# touch_rev2.net
KiCad netlist of a schematic drawn in EAGLE
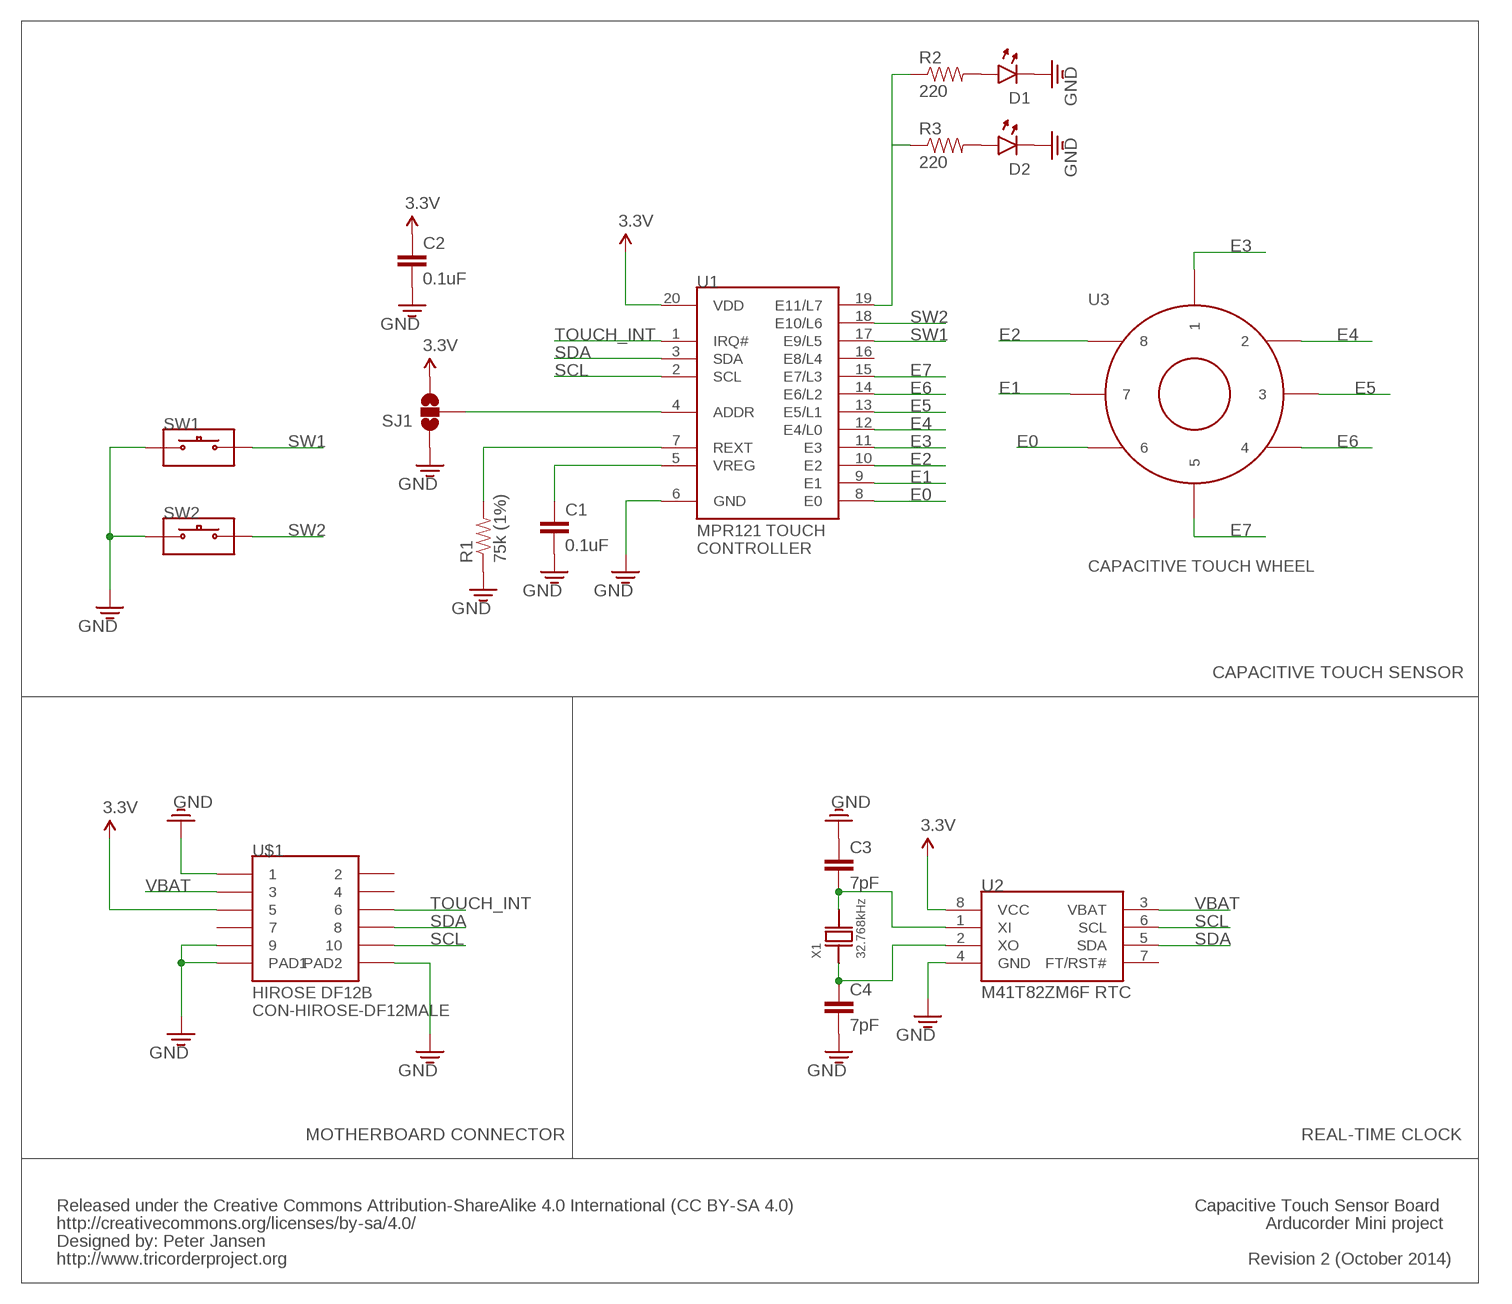
[diagram p0: schematic, sheet 1]

(export (version "E")
  (design (tool "Eeschema 10.0.6"))
  (components
    (comp (ref "C1")
      (value "0.1uF")
      (footprint "eagle-import:0603")
      (libsource (lib "eagle-import") (part "CAP0603"))
    )
    (comp (ref "C2")
      (value "0.1uF")
      (footprint "eagle-import:0603")
      (libsource (lib "eagle-import") (part "CAP0603"))
    )
    (comp (ref "C3")
      (value "7pF")
      (footprint "eagle-import:0603")
      (libsource (lib "eagle-import") (part "CAP0603"))
    )
    (comp (ref "C4")
      (value "7pF")
      (footprint "eagle-import:0603")
      (libsource (lib "eagle-import") (part "CAP0603"))
    )
    (comp (ref "D1")
      (value "0605-LED")
      (footprint "eagle-import:0603-LED")
      (libsource (lib "eagle-import") (part "0605-LED"))
    )
    (comp (ref "D2")
      (value "0605-LED")
      (footprint "eagle-import:0603-LED")
      (libsource (lib "eagle-import") (part "0605-LED"))
    )
    (comp (ref "R1")
      (value "75k (1%)")
      (footprint "eagle-import:0603")
      (libsource (lib "eagle-import") (part "RESISTOR0603"))
    )
    (comp (ref "R2")
      (value "220")
      (footprint "eagle-import:0603")
      (libsource (lib "eagle-import") (part "RESISTOR0603"))
    )
    (comp (ref "R3")
      (value "220")
      (footprint "eagle-import:0603")
      (libsource (lib "eagle-import") (part "RESISTOR0603"))
    )
    (comp (ref "SJ1")
      (value "SOLDERJUMPER_2WAYPASTE1&2")
      (footprint "eagle-import:SJ_3_PASTE1&2")
      (libsource (lib "eagle-import") (part "SOLDERJUMPER_2WAYPASTE1&2"))
    )
    (comp (ref "SW1")
      (value "SWITCH")
      (footprint "eagle-import:KMT071")
      (libsource (lib "eagle-import") (part "SWITCH"))
    )
    (comp (ref "SW2")
      (value "SWITCH")
      (footprint "eagle-import:KMT071")
      (libsource (lib "eagle-import") (part "SWITCH"))
    )
    (comp (ref "U$1")
      (value "CON-HIROSE-DF12MALE")
      (footprint "eagle-import:DF12B(3.0)-10DS-0.5V(86)")
      (libsource (lib "eagle-import") (part "CON-HIROSE-DF12MALE"))
    )
    (comp (ref "U1")
      (value "MPR121-TOUCH-CONTROLLER")
      (footprint "eagle-import:QFN-3X3-20")
      (libsource (lib "eagle-import") (part "MPR121-TOUCH-CONTROLLER"))
    )
    (comp (ref "U2")
      (value "M41T82ZM6F")
      (footprint "eagle-import:8-SOIC")
      (libsource (lib "eagle-import") (part "M41T82ZM6F"))
    )
    (comp (ref "U3")
      (value "CAPACITIVE-WHEEL-8")
      (footprint "eagle-import:CAPACITIVE-WHEEL-8")
      (libsource (lib "eagle-import") (part "CAPACITIVE-WHEEL-8"))
    )
    (comp (ref "X1")
      (value "32.768kHz")
      (footprint "eagle-import:CRYSTAL-9HT10")
      (libsource (lib "eagle-import") (part "CRYSTAL"))
    )
  )
  (nets
    (net (code "1") (name "/E0") (class "Default")
      (node (ref "U1") (pin "8") (pinfunction "E0_8") (pintype "bidirectional"))
      (node (ref "U3") (pin "6") (pinfunction "6_6") (pintype "bidirectional"))
    )
    (net (code "2") (name "/E1") (class "Default")
      (node (ref "U1") (pin "9") (pinfunction "E1_9") (pintype "bidirectional"))
      (node (ref "U3") (pin "7") (pinfunction "7_7") (pintype "bidirectional"))
    )
    (net (code "3") (name "/E2") (class "Default")
      (node (ref "U1") (pin "10") (pinfunction "E2_10") (pintype "bidirectional"))
      (node (ref "U3") (pin "8") (pinfunction "8_8") (pintype "bidirectional"))
    )
    (net (code "4") (name "/E3") (class "Default")
      (node (ref "U1") (pin "11") (pinfunction "E3_11") (pintype "bidirectional"))
      (node (ref "U3") (pin "1") (pinfunction "1_1") (pintype "bidirectional"))
    )
    (net (code "5") (name "/E4") (class "Default")
      (node (ref "U1") (pin "12") (pinfunction "E4/L0_12") (pintype "bidirectional"))
      (node (ref "U3") (pin "2") (pinfunction "2_2") (pintype "bidirectional"))
    )
    (net (code "6") (name "/E5") (class "Default")
      (node (ref "U1") (pin "13") (pinfunction "E5/L1_13") (pintype "bidirectional"))
      (node (ref "U3") (pin "3") (pinfunction "3_3") (pintype "bidirectional"))
    )
    (net (code "7") (name "/E6") (class "Default")
      (node (ref "U1") (pin "14") (pinfunction "E6/L2_14") (pintype "bidirectional"))
      (node (ref "U3") (pin "4") (pinfunction "4_4") (pintype "bidirectional"))
    )
    (net (code "8") (name "/E7") (class "Default")
      (node (ref "U1") (pin "15") (pinfunction "E7/L3_15") (pintype "bidirectional"))
      (node (ref "U3") (pin "5") (pinfunction "5_5") (pintype "bidirectional"))
    )
    (net (code "9") (name "/SCL") (class "Default")
      (node (ref "U$1") (pin "10") (pinfunction "10_10") (pintype "bidirectional"))
      (node (ref "U1") (pin "2") (pinfunction "SCL_2") (pintype "bidirectional"))
      (node (ref "U2") (pin "6") (pinfunction "SCL_6") (pintype "bidirectional"))
    )
    (net (code "10") (name "/SDA") (class "Default")
      (node (ref "U$1") (pin "8") (pinfunction "8_8") (pintype "bidirectional"))
      (node (ref "U1") (pin "3") (pinfunction "SDA_3") (pintype "bidirectional"))
      (node (ref "U2") (pin "5") (pinfunction "SDA_5") (pintype "bidirectional"))
    )
    (net (code "11") (name "/SW1") (class "Default")
      (node (ref "SW1") (pin "2A") (pinfunction "2A_2A") (pintype "bidirectional"))
      (node (ref "U1") (pin "17") (pinfunction "E9/L5_17") (pintype "bidirectional"))
    )
    (net (code "12") (name "/SW2") (class "Default")
      (node (ref "SW2") (pin "2A") (pinfunction "2A_2A") (pintype "bidirectional"))
      (node (ref "U1") (pin "18") (pinfunction "E10/L6_18") (pintype "bidirectional"))
    )
    (net (code "13") (name "/TOUCH_INT") (class "Default")
      (node (ref "U$1") (pin "6") (pinfunction "6_6") (pintype "bidirectional"))
      (node (ref "U1") (pin "1") (pinfunction "IRQ#_1") (pintype "bidirectional"))
    )
    (net (code "14") (name "/VBAT") (class "Default")
      (node (ref "U$1") (pin "3") (pinfunction "3_3") (pintype "bidirectional"))
      (node (ref "U2") (pin "3") (pinfunction "VBAT_3") (pintype "bidirectional"))
    )
    (net (code "15") (name "3.3V") (class "Default")
      (node (ref "C2") (pin "1") (pinfunction "1_1") (pintype "passive"))
      (node (ref "SJ1") (pin "3") (pinfunction "3_3") (pintype "passive"))
      (node (ref "U$1") (pin "5") (pinfunction "5_5") (pintype "bidirectional"))
      (node (ref "U1") (pin "20") (pinfunction "VDD_20") (pintype "bidirectional"))
      (node (ref "U2") (pin "8") (pinfunction "VCC_8") (pintype "bidirectional"))
    )
    (net (code "16") (name "GND") (class "Default")
      (node (ref "C1") (pin "2") (pinfunction "2_2") (pintype "passive"))
      (node (ref "C2") (pin "2") (pinfunction "2_2") (pintype "passive"))
      (node (ref "C3") (pin "1") (pinfunction "1_1") (pintype "passive"))
      (node (ref "C4") (pin "2") (pinfunction "2_2") (pintype "passive"))
      (node (ref "D1") (pin "CATHODE") (pinfunction "CATHODE_CATHODE") (pintype "bidirectional"))
      (node (ref "D2") (pin "CATHODE") (pinfunction "CATHODE_CATHODE") (pintype "bidirectional"))
      (node (ref "R1") (pin "1") (pinfunction "1_1") (pintype "passive"))
      (node (ref "SJ1") (pin "1") (pinfunction "1_1") (pintype "passive"))
      (node (ref "SW1") (pin "1A") (pinfunction "1A_1A") (pintype "bidirectional"))
      (node (ref "SW2") (pin "1A") (pinfunction "1A_1A") (pintype "bidirectional"))
      (node (ref "U$1") (pin "1") (pinfunction "1_1") (pintype "bidirectional"))
      (node (ref "U$1") (pin "9") (pinfunction "9_9") (pintype "bidirectional"))
      (node (ref "U$1") (pin "PAD1") (pinfunction "PAD1_PAD1") (pintype "bidirectional"))
      (node (ref "U$1") (pin "PAD2") (pinfunction "PAD2_PAD2") (pintype "bidirectional"))
      (node (ref "U1") (pin "6") (pinfunction "GND_6") (pintype "bidirectional"))
      (node (ref "U2") (pin "4") (pinfunction "GND_4") (pintype "bidirectional"))
    )
    (net (code "17") (name "Net-(D1-PadANODE)") (class "Default")
      (node (ref "D1") (pin "ANODE") (pinfunction "ANODE_ANODE") (pintype "bidirectional"))
      (node (ref "R2") (pin "2") (pinfunction "2_2") (pintype "passive"))
    )
    (net (code "18") (name "Net-(D2-PadANODE)") (class "Default")
      (node (ref "D2") (pin "ANODE") (pinfunction "ANODE_ANODE") (pintype "bidirectional"))
      (node (ref "R3") (pin "2") (pinfunction "2_2") (pintype "passive"))
    )
    (net (code "19") (name "Net-(U1-ADDR)") (class "Default")
      (node (ref "SJ1") (pin "2") (pinfunction "2_2") (pintype "passive"))
      (node (ref "U1") (pin "4") (pinfunction "ADDR_4") (pintype "bidirectional"))
    )
    (net (code "20") (name "Net-(U1-E11{slash}L7)") (class "Default")
      (node (ref "R2") (pin "1") (pinfunction "1_1") (pintype "passive"))
      (node (ref "R3") (pin "1") (pinfunction "1_1") (pintype "passive"))
      (node (ref "U1") (pin "19") (pinfunction "E11/L7_19") (pintype "bidirectional"))
    )
    (net (code "21") (name "Net-(U1-REXT)") (class "Default")
      (node (ref "R1") (pin "2") (pinfunction "2_2") (pintype "passive"))
      (node (ref "U1") (pin "7") (pinfunction "REXT_7") (pintype "bidirectional"))
    )
    (net (code "22") (name "Net-(U1-VREG)") (class "Default")
      (node (ref "C1") (pin "1") (pinfunction "1_1") (pintype "passive"))
      (node (ref "U1") (pin "5") (pinfunction "VREG_5") (pintype "bidirectional"))
    )
    (net (code "23") (name "Net-(U2-XI)") (class "Default")
      (node (ref "C3") (pin "2") (pinfunction "2_2") (pintype "passive"))
      (node (ref "U2") (pin "1") (pinfunction "XI_1") (pintype "bidirectional"))
      (node (ref "X1") (pin "2") (pinfunction "2_2") (pintype "bidirectional"))
    )
    (net (code "24") (name "Net-(U2-XO)") (class "Default")
      (node (ref "C4") (pin "1") (pinfunction "1_1") (pintype "passive"))
      (node (ref "U2") (pin "2") (pinfunction "XO_2") (pintype "bidirectional"))
      (node (ref "X1") (pin "1") (pinfunction "1_1") (pintype "bidirectional"))
    )
    (net (code "25") (name "unconnected-(U$1-Pad2)") (class "Default")
      (node (ref "U$1") (pin "2") (pinfunction "2_2") (pintype "bidirectional"))
    )
    (net (code "26") (name "unconnected-(U$1-Pad4)") (class "Default")
      (node (ref "U$1") (pin "4") (pinfunction "4_4") (pintype "bidirectional"))
    )
    (net (code "27") (name "unconnected-(U$1-Pad7)") (class "Default")
      (node (ref "U$1") (pin "7") (pinfunction "7_7") (pintype "bidirectional"))
    )
    (net (code "28") (name "unconnected-(U1-E8{slash}L4-Pad16)") (class "Default")
      (node (ref "U1") (pin "16") (pinfunction "E8/L4_16") (pintype "bidirectional"))
    )
    (net (code "29") (name "unconnected-(U2-FT{slash}RST#-Pad7)") (class "Default")
      (node (ref "U2") (pin "7") (pinfunction "FT/RST#_7") (pintype "bidirectional"))
    )
  )
)
